# Schematic.net
KiCad netlist of a schematic drawn in EAGLE
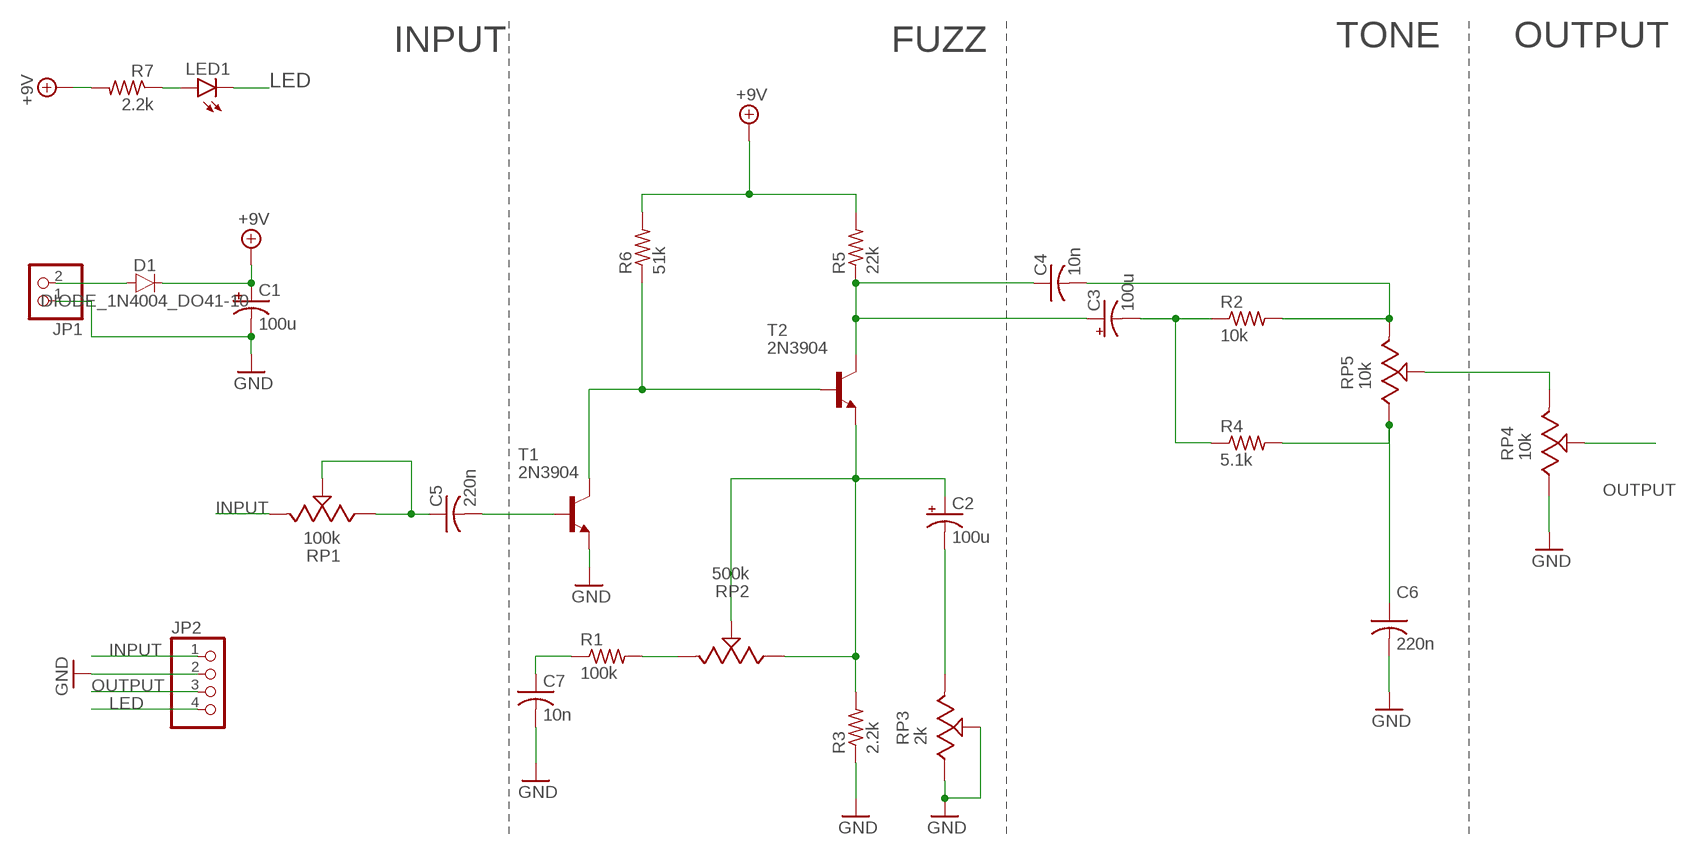
[diagram p0: schematic, sheet 1]

(export (version "E")
  (design (tool "Eeschema 10.0.6"))
  (components
    (comp (ref "C1")
      (value "100u")
      (footprint "eagle-import:140CLH-0810")
      (libsource (lib "eagle-import") (part "CPOL-US140CLH-0810"))
    )
    (comp (ref "C2")
      (value "100u")
      (footprint "eagle-import:140CLH-0810")
      (libsource (lib "eagle-import") (part "CPOL-US140CLH-0810"))
    )
    (comp (ref "C3")
      (value "100u")
      (footprint "eagle-import:140CLH-0810")
      (libsource (lib "eagle-import") (part "CPOL-US140CLH-0810"))
    )
    (comp (ref "C4")
      (value "10n")
      (footprint "eagle-import:C0805")
      (libsource (lib "eagle-import") (part "C-USC0805"))
    )
    (comp (ref "C5")
      (value "220n")
      (footprint "eagle-import:C0805")
      (libsource (lib "eagle-import") (part "C-USC0805"))
    )
    (comp (ref "C6")
      (value "220n")
      (footprint "eagle-import:C0805")
      (libsource (lib "eagle-import") (part "C-USC0805"))
    )
    (comp (ref "C7")
      (value "10n")
      (footprint "eagle-import:C0805")
      (libsource (lib "eagle-import") (part "C-USC0805"))
    )
    (comp (ref "D1")
      (value "DIODE_1N4004_DO41-10")
      (footprint "eagle-import:DO41-10")
      (fields (field (name "MANUFACTURER") "onsemi") (field (name "MPN") "1N4004"))
      (libsource (lib "eagle-import") (part "DIODE__DO41-101N4004"))
    )
    (comp (ref "JP1")
      (value "PINHD-1X2")
      (footprint "eagle-import:1X02")
      (libsource (lib "eagle-import") (part "PINHD-1X2"))
    )
    (comp (ref "JP2")
      (value "PINHD-1X4")
      (footprint "eagle-import:1X04")
      (libsource (lib "eagle-import") (part "PINHD-1X4"))
    )
    (comp (ref "LED1")
      (value "LED5MM")
      (footprint "eagle-import:LED5MM")
      (libsource (lib "eagle-import") (part "LED5MM"))
    )
    (comp (ref "R1")
      (value "100k")
      (footprint "eagle-import:R0805")
      (libsource (lib "eagle-import") (part "R-US_R0805"))
    )
    (comp (ref "R2")
      (value "10k")
      (footprint "eagle-import:R0805")
      (libsource (lib "eagle-import") (part "R-US_R0805"))
    )
    (comp (ref "R3")
      (value "2.2k")
      (footprint "eagle-import:R0805")
      (libsource (lib "eagle-import") (part "R-US_R0805"))
    )
    (comp (ref "R4")
      (value "5.1k")
      (footprint "eagle-import:R0805")
      (libsource (lib "eagle-import") (part "R-US_R0805"))
    )
    (comp (ref "R5")
      (value "22k")
      (footprint "eagle-import:R0805")
      (libsource (lib "eagle-import") (part "R-US_R0805"))
    )
    (comp (ref "R6")
      (value "51k")
      (footprint "eagle-import:R0805")
      (libsource (lib "eagle-import") (part "R-US_R0805"))
    )
    (comp (ref "R7")
      (value "2.2k")
      (footprint "eagle-import:R0805")
      (libsource (lib "eagle-import") (part "R-US_R0805"))
    )
    (comp (ref "RP1")
      (value "100k")
      (footprint "eagle-import:PTV09A-X")
      (libsource (lib "eagle-import") (part "PTV09A-X-US"))
    )
    (comp (ref "RP2")
      (value "500k")
      (footprint "eagle-import:PTV09A-X")
      (libsource (lib "eagle-import") (part "PTV09A-X-US"))
    )
    (comp (ref "RP3")
      (value "2k")
      (footprint "eagle-import:PTV09A-X")
      (libsource (lib "eagle-import") (part "PTV09A-X-US"))
    )
    (comp (ref "RP4")
      (value "10k")
      (footprint "eagle-import:PTV09A-X")
      (libsource (lib "eagle-import") (part "PTV09A-X-US"))
    )
    (comp (ref "RP5")
      (value "10k")
      (footprint "eagle-import:PTV09A-X")
      (libsource (lib "eagle-import") (part "PTV09A-X-US"))
    )
    (comp (ref "T1")
      (value "2N3904")
      (footprint "eagle-import:TO92")
      (libsource (lib "eagle-import") (part "2N3904"))
    )
    (comp (ref "T2")
      (value "2N3904")
      (footprint "eagle-import:TO92")
      (libsource (lib "eagle-import") (part "2N3904"))
    )
  )
  (nets
    (net (code "1") (name "+9V") (class "Default")
      (node (ref "C1") (pin "+") (pinfunction "+_+") (pintype "passive"))
      (node (ref "D1") (pin "C") (pinfunction "C_C") (pintype "passive"))
      (node (ref "R5") (pin "2") (pinfunction "2_2") (pintype "passive"))
      (node (ref "R6") (pin "2") (pinfunction "2_2") (pintype "passive"))
      (node (ref "R7") (pin "2") (pinfunction "2_2") (pintype "passive"))
    )
    (net (code "2") (name "/INPUT") (class "Default")
      (node (ref "JP2") (pin "1") (pinfunction "1_1") (pintype "passive"))
      (node (ref "RP1") (pin "1") (pinfunction "1_1") (pintype "passive"))
    )
    (net (code "3") (name "/LED") (class "Default")
      (node (ref "JP2") (pin "4") (pinfunction "4_4") (pintype "passive"))
      (node (ref "LED1") (pin "K") (pinfunction "C_K") (pintype "passive"))
    )
    (net (code "4") (name "/OUTPUT") (class "Default")
      (node (ref "JP2") (pin "3") (pinfunction "3_3") (pintype "passive"))
      (node (ref "RP4") (pin "2") (pinfunction "2_2") (pintype "passive"))
    )
    (net (code "5") (name "GND") (class "Default")
      (node (ref "C1") (pin "-") (pinfunction "-_-") (pintype "passive"))
      (node (ref "C6") (pin "2") (pinfunction "2_2") (pintype "passive"))
      (node (ref "C7") (pin "2") (pinfunction "2_2") (pintype "passive"))
      (node (ref "JP1") (pin "1") (pinfunction "1_1") (pintype "passive"))
      (node (ref "JP2") (pin "2") (pinfunction "2_2") (pintype "passive"))
      (node (ref "R3") (pin "1") (pinfunction "1_1") (pintype "passive"))
      (node (ref "RP3") (pin "2") (pinfunction "2_2") (pintype "passive"))
      (node (ref "RP3") (pin "3") (pinfunction "3_3") (pintype "passive"))
      (node (ref "RP4") (pin "3") (pinfunction "3_3") (pintype "passive"))
      (node (ref "T1") (pin "3") (pinfunction "E_3") (pintype "passive"))
    )
    (net (code "6") (name "Net-(C2-Pad-)") (class "Default")
      (node (ref "C2") (pin "-") (pinfunction "-_-") (pintype "passive"))
      (node (ref "RP3") (pin "1") (pinfunction "1_1") (pintype "passive"))
    )
    (net (code "7") (name "Net-(C3-Pad-)") (class "Default")
      (node (ref "C3") (pin "-") (pinfunction "-_-") (pintype "passive"))
      (node (ref "R2") (pin "1") (pinfunction "1_1") (pintype "passive"))
      (node (ref "R4") (pin "1") (pinfunction "1_1") (pintype "passive"))
    )
    (net (code "8") (name "Net-(C4-Pad2)") (class "Default")
      (node (ref "C4") (pin "2") (pinfunction "2_2") (pintype "passive"))
      (node (ref "R2") (pin "2") (pinfunction "2_2") (pintype "passive"))
      (node (ref "RP5") (pin "1") (pinfunction "1_1") (pintype "passive"))
    )
    (net (code "9") (name "Net-(C5-Pad1)") (class "Default")
      (node (ref "C5") (pin "1") (pinfunction "1_1") (pintype "passive"))
      (node (ref "RP1") (pin "2") (pinfunction "2_2") (pintype "passive"))
      (node (ref "RP1") (pin "3") (pinfunction "3_3") (pintype "passive"))
    )
    (net (code "10") (name "Net-(C6-Pad1)") (class "Default")
      (node (ref "C6") (pin "1") (pinfunction "1_1") (pintype "passive"))
      (node (ref "R4") (pin "2") (pinfunction "2_2") (pintype "passive"))
      (node (ref "RP5") (pin "3") (pinfunction "3_3") (pintype "passive"))
    )
    (net (code "11") (name "Net-(C7-Pad1)") (class "Default")
      (node (ref "C7") (pin "1") (pinfunction "1_1") (pintype "passive"))
      (node (ref "R1") (pin "1") (pinfunction "1_1") (pintype "passive"))
    )
    (net (code "12") (name "Net-(D1-PadA)") (class "Default")
      (node (ref "D1") (pin "A") (pinfunction "A_A") (pintype "passive"))
      (node (ref "JP1") (pin "2") (pinfunction "2_2") (pintype "passive"))
    )
    (net (code "13") (name "Net-(LED1-PadA)") (class "Default")
      (node (ref "LED1") (pin "A") (pinfunction "A_A") (pintype "passive"))
      (node (ref "R7") (pin "1") (pinfunction "1_1") (pintype "passive"))
    )
    (net (code "14") (name "Net-(R1-Pad2)") (class "Default")
      (node (ref "R1") (pin "2") (pinfunction "2_2") (pintype "passive"))
      (node (ref "RP2") (pin "1") (pinfunction "1_1") (pintype "passive"))
    )
    (net (code "15") (name "Net-(RP4-Pad1)") (class "Default")
      (node (ref "RP4") (pin "1") (pinfunction "1_1") (pintype "passive"))
      (node (ref "RP5") (pin "2") (pinfunction "2_2") (pintype "passive"))
    )
    (net (code "16") (name "Net-(T1-B)") (class "Default")
      (node (ref "C5") (pin "2") (pinfunction "2_2") (pintype "passive"))
      (node (ref "T1") (pin "2") (pinfunction "B_2") (pintype "passive"))
    )
    (net (code "17") (name "Net-(T1-C)") (class "Default")
      (node (ref "R6") (pin "1") (pinfunction "1_1") (pintype "passive"))
      (node (ref "T1") (pin "1") (pinfunction "C_1") (pintype "passive"))
      (node (ref "T2") (pin "2") (pinfunction "B_2") (pintype "passive"))
    )
    (net (code "18") (name "Net-(T2-C)") (class "Default")
      (node (ref "C3") (pin "+") (pinfunction "+_+") (pintype "passive"))
      (node (ref "C4") (pin "1") (pinfunction "1_1") (pintype "passive"))
      (node (ref "R5") (pin "1") (pinfunction "1_1") (pintype "passive"))
      (node (ref "T2") (pin "1") (pinfunction "C_1") (pintype "passive"))
    )
    (net (code "19") (name "Net-(T2-E)") (class "Default")
      (node (ref "C2") (pin "+") (pinfunction "+_+") (pintype "passive"))
      (node (ref "R3") (pin "2") (pinfunction "2_2") (pintype "passive"))
      (node (ref "RP2") (pin "2") (pinfunction "2_2") (pintype "passive"))
      (node (ref "RP2") (pin "3") (pinfunction "3_3") (pintype "passive"))
      (node (ref "T2") (pin "3") (pinfunction "E_3") (pintype "passive"))
    )
  )
)
